# SENSE.net
KiCad netlist of a schematic drawn in Altium Designer
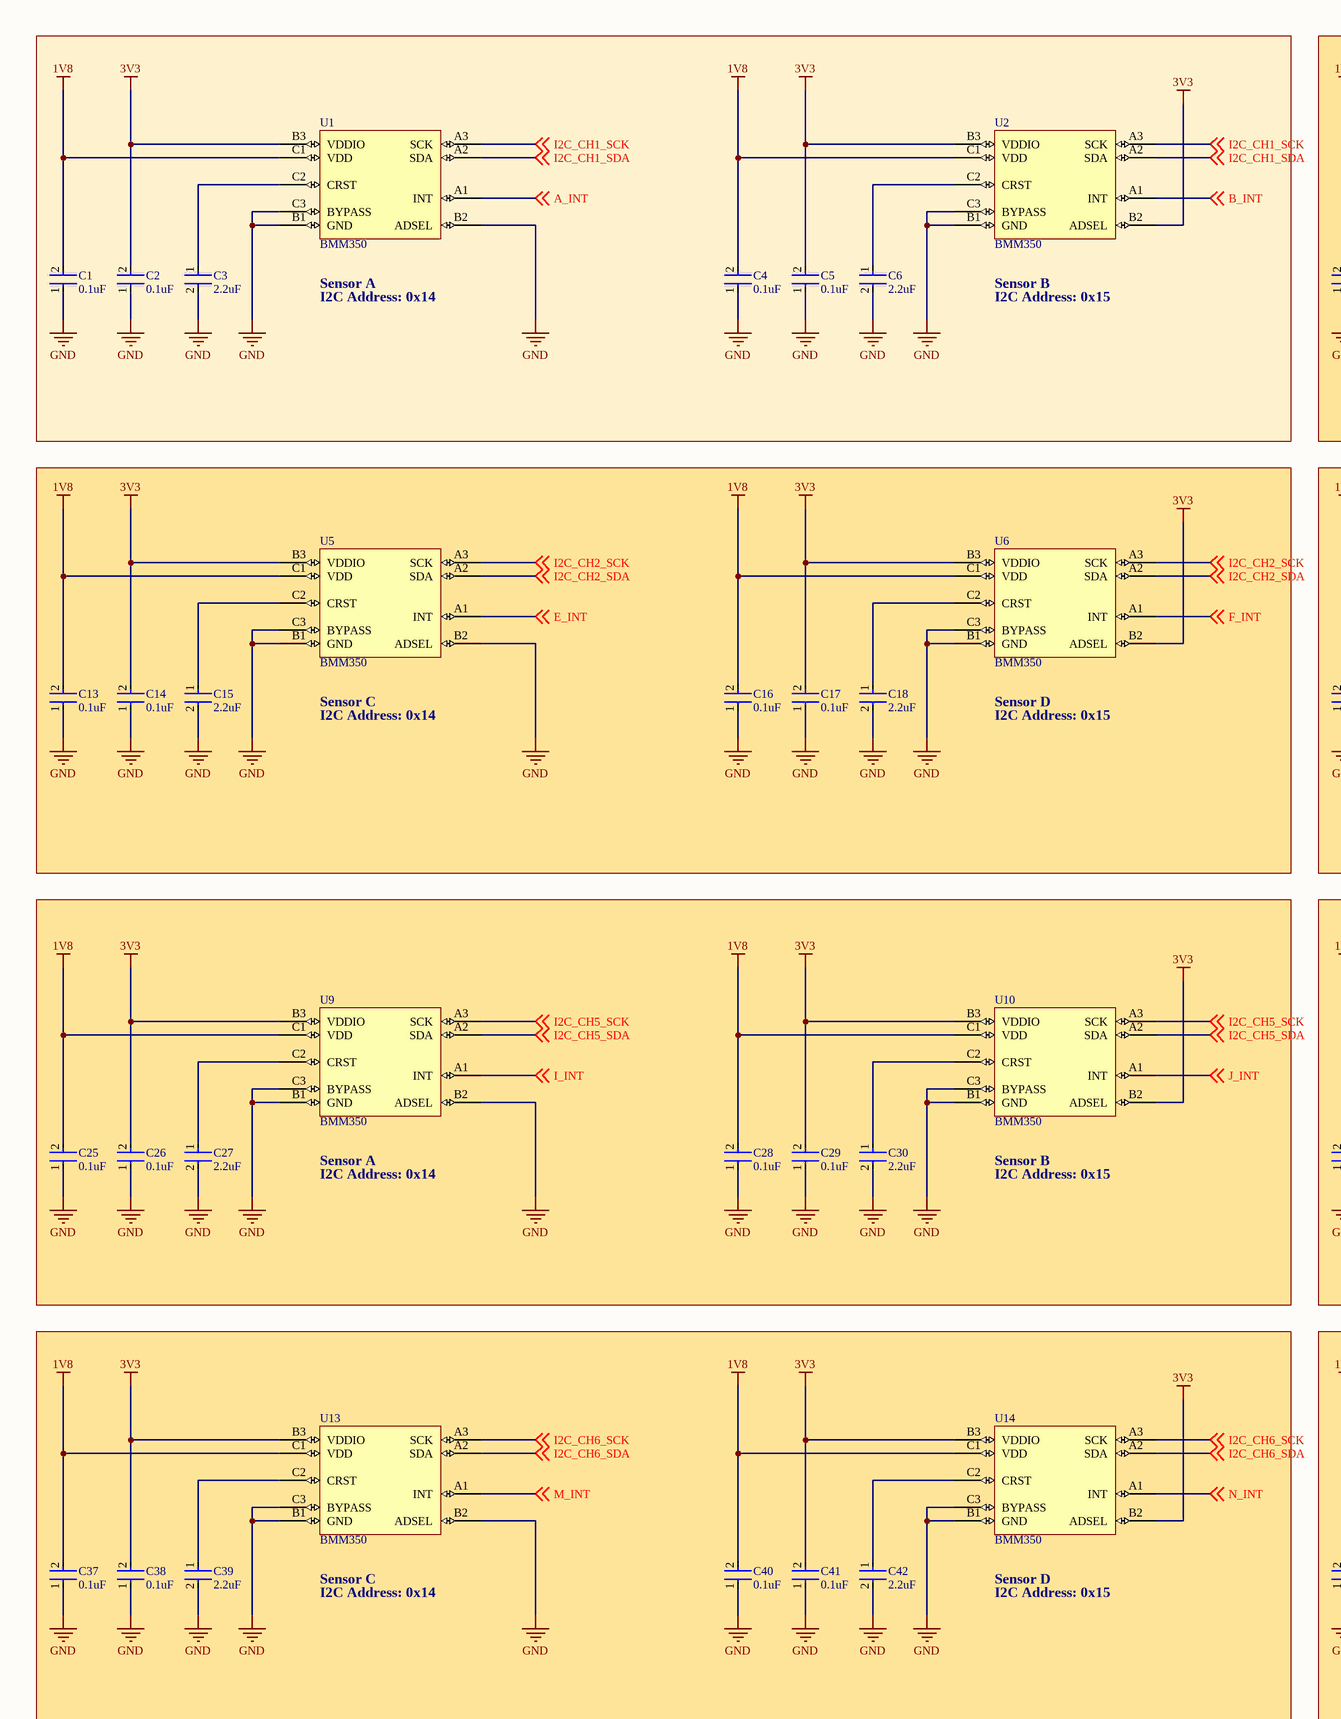
[diagram p0: SENSE.SchDoc, left]
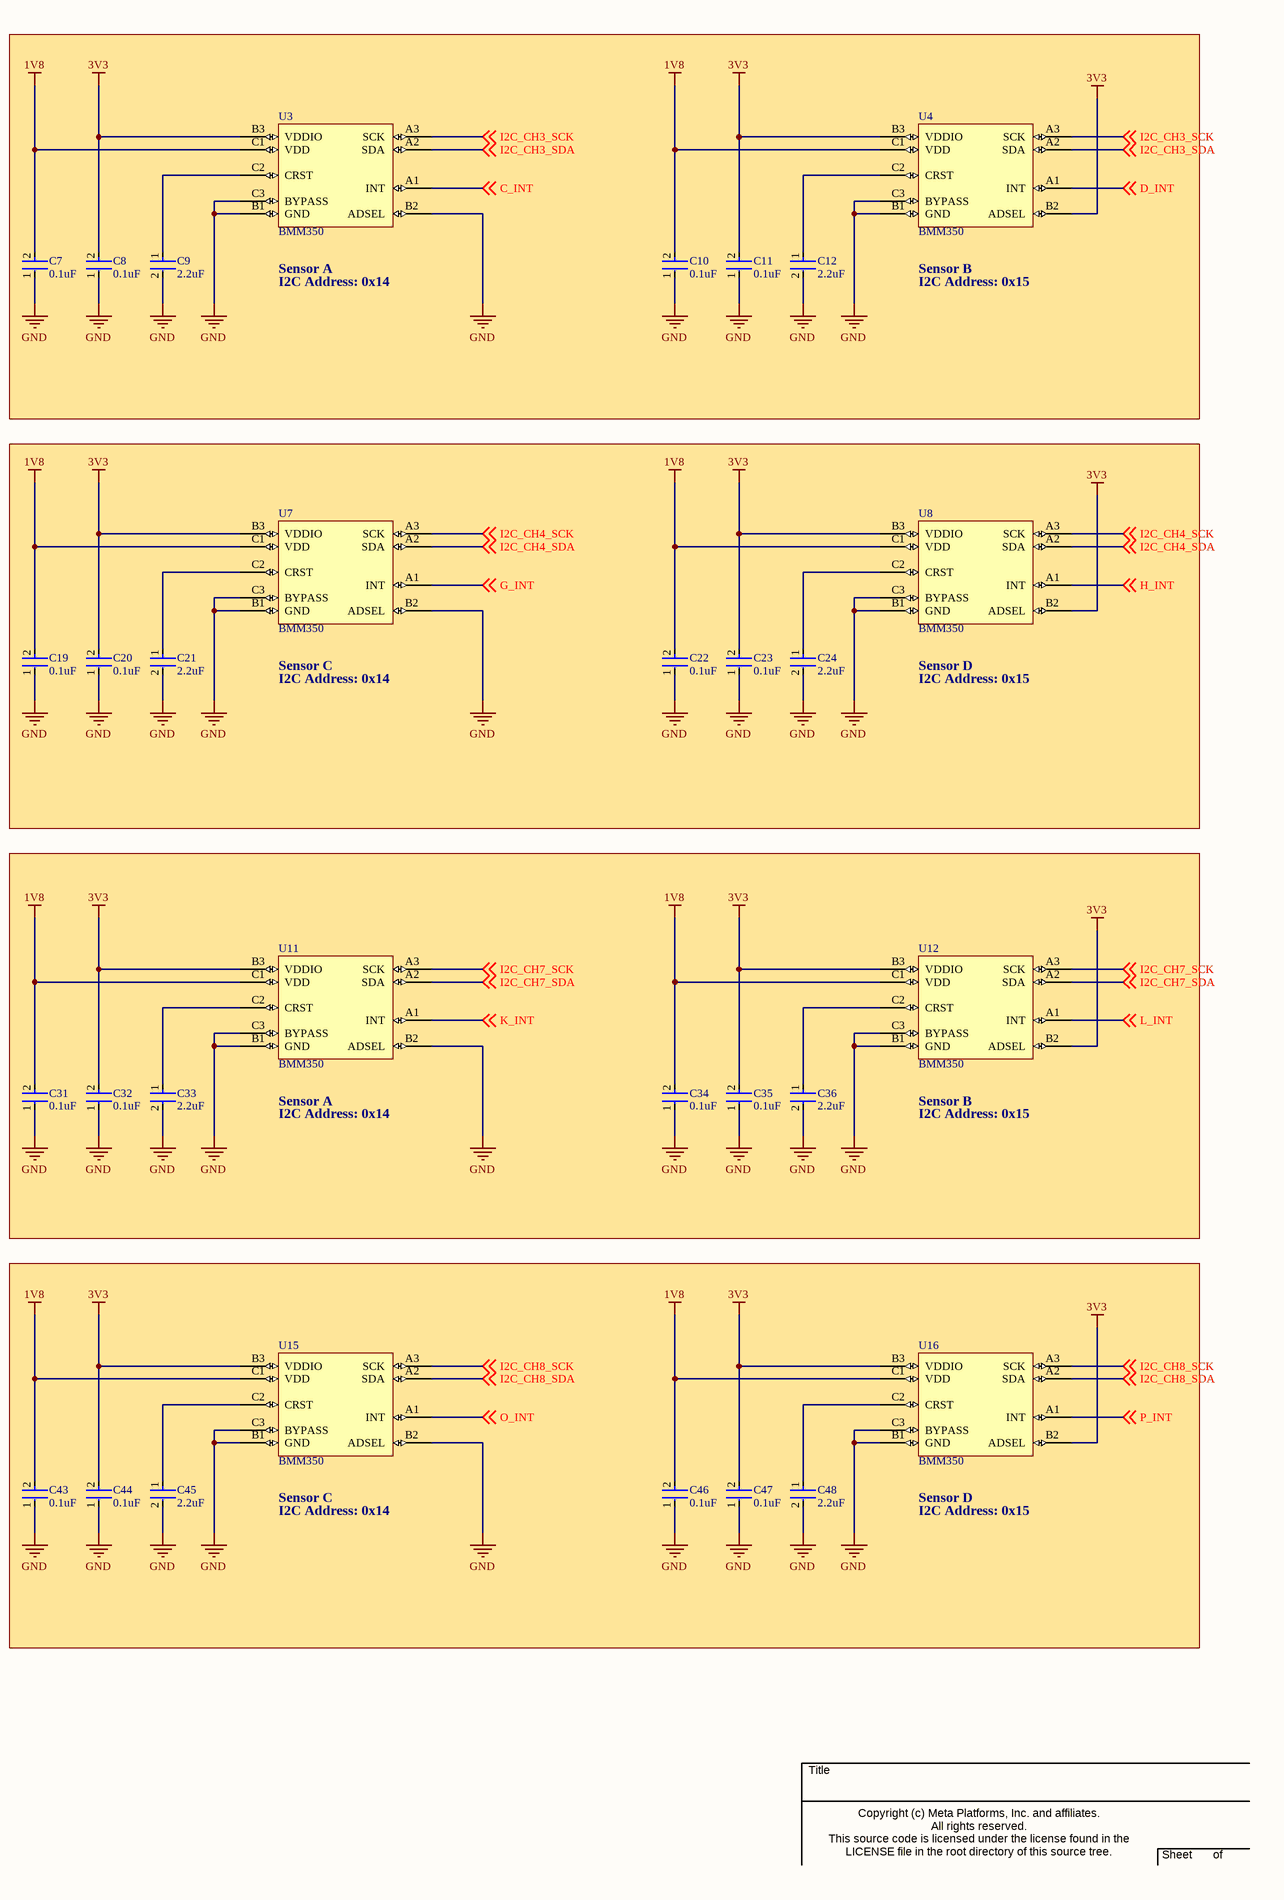
[diagram p1: SENSE.SchDoc, right]

(export (version "E")
  (design (tool "Eeschema 10.0.6"))
  (components
    (comp (ref "C1")
      (value "0.1uF")
      (footprint "FP-GRM15-MFG")
      (description "CAP CER 0.1UF 16V X7R 0402")
      (fields (field (name "MANUFACTURER PART NUMBER") "GRM155R71C104KA88D") (field (name "TOLERANCE") "10%"))
      (libsource (lib "Altium Content Vault") (part "236180d848d6139a670b325ea6854c9"))
    )
    (comp (ref "C2")
      (value "0.1uF")
      (footprint "FP-GRM15-MFG")
      (description "CAP CER 0.1UF 16V X7R 0402")
      (fields (field (name "MANUFACTURER PART NUMBER") "GRM155R71C104KA88D") (field (name "TOLERANCE") "10%"))
      (libsource (lib "Altium Content Vault") (part "236180d848d6139a670b325ea6854c9"))
    )
    (comp (ref "C3")
      (value "2.2uF")
      (footprint "FP-C1005-050-0_15-0_1-MFG")
      (description "CAP CER 2.2UF 10V X7S 0402")
      (fields (field (name "TOLERANCE") "10%"))
      (libsource (lib "Altium Content Vault") (part "b4654b650e69147ec39a6b967a45e02"))
    )
    (comp (ref "C4")
      (value "0.1uF")
      (footprint "FP-GRM15-MFG")
      (description "CAP CER 0.1UF 16V X7R 0402")
      (fields (field (name "MANUFACTURER PART NUMBER") "GRM155R71C104KA88D") (field (name "TOLERANCE") "10%"))
      (libsource (lib "Altium Content Vault") (part "236180d848d6139a670b325ea6854c9"))
    )
    (comp (ref "C5")
      (value "0.1uF")
      (footprint "FP-GRM15-MFG")
      (description "CAP CER 0.1UF 16V X7R 0402")
      (fields (field (name "MANUFACTURER PART NUMBER") "GRM155R71C104KA88D") (field (name "TOLERANCE") "10%"))
      (libsource (lib "Altium Content Vault") (part "236180d848d6139a670b325ea6854c9"))
    )
    (comp (ref "C6")
      (value "2.2uF")
      (footprint "FP-C1005-050-0_15-0_1-MFG")
      (description "CAP CER 2.2UF 10V X7S 0402")
      (fields (field (name "TOLERANCE") "10%"))
      (libsource (lib "Altium Content Vault") (part "b4654b650e69147ec39a6b967a45e02"))
    )
    (comp (ref "C7")
      (value "0.1uF")
      (footprint "FP-GRM15-MFG")
      (description "CAP CER 0.1UF 16V X7R 0402")
      (fields (field (name "MANUFACTURER PART NUMBER") "GRM155R71C104KA88D") (field (name "TOLERANCE") "10%"))
      (libsource (lib "Altium Content Vault") (part "236180d848d6139a670b325ea6854c9"))
    )
    (comp (ref "C8")
      (value "0.1uF")
      (footprint "FP-GRM15-MFG")
      (description "CAP CER 0.1UF 16V X7R 0402")
      (fields (field (name "MANUFACTURER PART NUMBER") "GRM155R71C104KA88D") (field (name "TOLERANCE") "10%"))
      (libsource (lib "Altium Content Vault") (part "236180d848d6139a670b325ea6854c9"))
    )
    (comp (ref "C9")
      (value "2.2uF")
      (footprint "FP-C1005-050-0_15-0_1-MFG")
      (description "CAP CER 2.2UF 10V X7S 0402")
      (fields (field (name "TOLERANCE") "10%"))
      (libsource (lib "Altium Content Vault") (part "b4654b650e69147ec39a6b967a45e02"))
    )
    (comp (ref "C10")
      (value "0.1uF")
      (footprint "FP-GRM15-MFG")
      (description "CAP CER 0.1UF 16V X7R 0402")
      (fields (field (name "MANUFACTURER PART NUMBER") "GRM155R71C104KA88D") (field (name "TOLERANCE") "10%"))
      (libsource (lib "Altium Content Vault") (part "236180d848d6139a670b325ea6854c9"))
    )
    (comp (ref "C11")
      (value "0.1uF")
      (footprint "FP-GRM15-MFG")
      (description "CAP CER 0.1UF 16V X7R 0402")
      (fields (field (name "MANUFACTURER PART NUMBER") "GRM155R71C104KA88D") (field (name "TOLERANCE") "10%"))
      (libsource (lib "Altium Content Vault") (part "236180d848d6139a670b325ea6854c9"))
    )
    (comp (ref "C12")
      (value "2.2uF")
      (footprint "FP-C1005-050-0_15-0_1-MFG")
      (description "CAP CER 2.2UF 10V X7S 0402")
      (fields (field (name "TOLERANCE") "10%"))
      (libsource (lib "Altium Content Vault") (part "b4654b650e69147ec39a6b967a45e02"))
    )
    (comp (ref "C13")
      (value "0.1uF")
      (footprint "FP-GRM15-MFG")
      (description "CAP CER 0.1UF 16V X7R 0402")
      (fields (field (name "MANUFACTURER PART NUMBER") "GRM155R71C104KA88D") (field (name "TOLERANCE") "10%"))
      (libsource (lib "Altium Content Vault") (part "236180d848d6139a670b325ea6854c9"))
    )
    (comp (ref "C14")
      (value "0.1uF")
      (footprint "FP-GRM15-MFG")
      (description "CAP CER 0.1UF 16V X7R 0402")
      (fields (field (name "MANUFACTURER PART NUMBER") "GRM155R71C104KA88D") (field (name "TOLERANCE") "10%"))
      (libsource (lib "Altium Content Vault") (part "236180d848d6139a670b325ea6854c9"))
    )
    (comp (ref "C15")
      (value "2.2uF")
      (footprint "FP-C1005-050-0_15-0_1-MFG")
      (description "CAP CER 2.2UF 10V X7S 0402")
      (fields (field (name "TOLERANCE") "10%"))
      (libsource (lib "Altium Content Vault") (part "b4654b650e69147ec39a6b967a45e02"))
    )
    (comp (ref "C16")
      (value "0.1uF")
      (footprint "FP-GRM15-MFG")
      (description "CAP CER 0.1UF 16V X7R 0402")
      (fields (field (name "MANUFACTURER PART NUMBER") "GRM155R71C104KA88D") (field (name "TOLERANCE") "10%"))
      (libsource (lib "Altium Content Vault") (part "236180d848d6139a670b325ea6854c9"))
    )
    (comp (ref "C17")
      (value "0.1uF")
      (footprint "FP-GRM15-MFG")
      (description "CAP CER 0.1UF 16V X7R 0402")
      (fields (field (name "MANUFACTURER PART NUMBER") "GRM155R71C104KA88D") (field (name "TOLERANCE") "10%"))
      (libsource (lib "Altium Content Vault") (part "236180d848d6139a670b325ea6854c9"))
    )
    (comp (ref "C18")
      (value "2.2uF")
      (footprint "FP-C1005-050-0_15-0_1-MFG")
      (description "CAP CER 2.2UF 10V X7S 0402")
      (fields (field (name "TOLERANCE") "10%"))
      (libsource (lib "Altium Content Vault") (part "b4654b650e69147ec39a6b967a45e02"))
    )
    (comp (ref "C19")
      (value "0.1uF")
      (footprint "FP-GRM15-MFG")
      (description "CAP CER 0.1UF 16V X7R 0402")
      (fields (field (name "MANUFACTURER PART NUMBER") "GRM155R71C104KA88D") (field (name "TOLERANCE") "10%"))
      (libsource (lib "Altium Content Vault") (part "236180d848d6139a670b325ea6854c9"))
    )
    (comp (ref "C20")
      (value "0.1uF")
      (footprint "FP-GRM15-MFG")
      (description "CAP CER 0.1UF 16V X7R 0402")
      (fields (field (name "MANUFACTURER PART NUMBER") "GRM155R71C104KA88D") (field (name "TOLERANCE") "10%"))
      (libsource (lib "Altium Content Vault") (part "236180d848d6139a670b325ea6854c9"))
    )
    (comp (ref "C21")
      (value "2.2uF")
      (footprint "FP-C1005-050-0_15-0_1-MFG")
      (description "CAP CER 2.2UF 10V X7S 0402")
      (fields (field (name "TOLERANCE") "10%"))
      (libsource (lib "Altium Content Vault") (part "b4654b650e69147ec39a6b967a45e02"))
    )
    (comp (ref "C22")
      (value "0.1uF")
      (footprint "FP-GRM15-MFG")
      (description "CAP CER 0.1UF 16V X7R 0402")
      (fields (field (name "MANUFACTURER PART NUMBER") "GRM155R71C104KA88D") (field (name "TOLERANCE") "10%"))
      (libsource (lib "Altium Content Vault") (part "236180d848d6139a670b325ea6854c9"))
    )
    (comp (ref "C23")
      (value "0.1uF")
      (footprint "FP-GRM15-MFG")
      (description "CAP CER 0.1UF 16V X7R 0402")
      (fields (field (name "MANUFACTURER PART NUMBER") "GRM155R71C104KA88D") (field (name "TOLERANCE") "10%"))
      (libsource (lib "Altium Content Vault") (part "236180d848d6139a670b325ea6854c9"))
    )
    (comp (ref "C24")
      (value "2.2uF")
      (footprint "FP-C1005-050-0_15-0_1-MFG")
      (description "CAP CER 2.2UF 10V X7S 0402")
      (fields (field (name "TOLERANCE") "10%"))
      (libsource (lib "Altium Content Vault") (part "b4654b650e69147ec39a6b967a45e02"))
    )
    (comp (ref "C25")
      (value "0.1uF")
      (footprint "FP-GRM15-MFG")
      (description "CAP CER 0.1UF 16V X7R 0402")
      (fields (field (name "MANUFACTURER PART NUMBER") "GRM155R71C104KA88D") (field (name "TOLERANCE") "10%"))
      (libsource (lib "Altium Content Vault") (part "236180d848d6139a670b325ea6854c9"))
    )
    (comp (ref "C26")
      (value "0.1uF")
      (footprint "FP-GRM15-MFG")
      (description "CAP CER 0.1UF 16V X7R 0402")
      (fields (field (name "MANUFACTURER PART NUMBER") "GRM155R71C104KA88D") (field (name "TOLERANCE") "10%"))
      (libsource (lib "Altium Content Vault") (part "236180d848d6139a670b325ea6854c9"))
    )
    (comp (ref "C27")
      (value "2.2uF")
      (footprint "FP-C1005-050-0_15-0_1-MFG")
      (description "CAP CER 2.2UF 10V X7S 0402")
      (fields (field (name "TOLERANCE") "10%"))
      (libsource (lib "Altium Content Vault") (part "b4654b650e69147ec39a6b967a45e02"))
    )
    (comp (ref "C28")
      (value "0.1uF")
      (footprint "FP-GRM15-MFG")
      (description "CAP CER 0.1UF 16V X7R 0402")
      (fields (field (name "MANUFACTURER PART NUMBER") "GRM155R71C104KA88D") (field (name "TOLERANCE") "10%"))
      (libsource (lib "Altium Content Vault") (part "236180d848d6139a670b325ea6854c9"))
    )
    (comp (ref "C29")
      (value "0.1uF")
      (footprint "FP-GRM15-MFG")
      (description "CAP CER 0.1UF 16V X7R 0402")
      (fields (field (name "MANUFACTURER PART NUMBER") "GRM155R71C104KA88D") (field (name "TOLERANCE") "10%"))
      (libsource (lib "Altium Content Vault") (part "236180d848d6139a670b325ea6854c9"))
    )
    (comp (ref "C30")
      (value "2.2uF")
      (footprint "FP-C1005-050-0_15-0_1-MFG")
      (description "CAP CER 2.2UF 10V X7S 0402")
      (fields (field (name "TOLERANCE") "10%"))
      (libsource (lib "Altium Content Vault") (part "b4654b650e69147ec39a6b967a45e02"))
    )
    (comp (ref "C31")
      (value "0.1uF")
      (footprint "FP-GRM15-MFG")
      (description "CAP CER 0.1UF 16V X7R 0402")
      (fields (field (name "MANUFACTURER PART NUMBER") "GRM155R71C104KA88D") (field (name "TOLERANCE") "10%"))
      (libsource (lib "Altium Content Vault") (part "236180d848d6139a670b325ea6854c9"))
    )
    (comp (ref "C32")
      (value "0.1uF")
      (footprint "FP-GRM15-MFG")
      (description "CAP CER 0.1UF 16V X7R 0402")
      (fields (field (name "MANUFACTURER PART NUMBER") "GRM155R71C104KA88D") (field (name "TOLERANCE") "10%"))
      (libsource (lib "Altium Content Vault") (part "236180d848d6139a670b325ea6854c9"))
    )
    (comp (ref "C33")
      (value "2.2uF")
      (footprint "FP-C1005-050-0_15-0_1-MFG")
      (description "CAP CER 2.2UF 10V X7S 0402")
      (fields (field (name "TOLERANCE") "10%"))
      (libsource (lib "Altium Content Vault") (part "b4654b650e69147ec39a6b967a45e02"))
    )
    (comp (ref "C34")
      (value "0.1uF")
      (footprint "FP-GRM15-MFG")
      (description "CAP CER 0.1UF 16V X7R 0402")
      (fields (field (name "MANUFACTURER PART NUMBER") "GRM155R71C104KA88D") (field (name "TOLERANCE") "10%"))
      (libsource (lib "Altium Content Vault") (part "236180d848d6139a670b325ea6854c9"))
    )
    (comp (ref "C35")
      (value "0.1uF")
      (footprint "FP-GRM15-MFG")
      (description "CAP CER 0.1UF 16V X7R 0402")
      (fields (field (name "MANUFACTURER PART NUMBER") "GRM155R71C104KA88D") (field (name "TOLERANCE") "10%"))
      (libsource (lib "Altium Content Vault") (part "236180d848d6139a670b325ea6854c9"))
    )
    (comp (ref "C36")
      (value "2.2uF")
      (footprint "FP-C1005-050-0_15-0_1-MFG")
      (description "CAP CER 2.2UF 10V X7S 0402")
      (fields (field (name "TOLERANCE") "10%"))
      (libsource (lib "Altium Content Vault") (part "b4654b650e69147ec39a6b967a45e02"))
    )
    (comp (ref "C37")
      (value "0.1uF")
      (footprint "FP-GRM15-MFG")
      (description "CAP CER 0.1UF 16V X7R 0402")
      (fields (field (name "MANUFACTURER PART NUMBER") "GRM155R71C104KA88D") (field (name "TOLERANCE") "10%"))
      (libsource (lib "Altium Content Vault") (part "236180d848d6139a670b325ea6854c9"))
    )
    (comp (ref "C38")
      (value "0.1uF")
      (footprint "FP-GRM15-MFG")
      (description "CAP CER 0.1UF 16V X7R 0402")
      (fields (field (name "MANUFACTURER PART NUMBER") "GRM155R71C104KA88D") (field (name "TOLERANCE") "10%"))
      (libsource (lib "Altium Content Vault") (part "236180d848d6139a670b325ea6854c9"))
    )
    (comp (ref "C39")
      (value "2.2uF")
      (footprint "FP-C1005-050-0_15-0_1-MFG")
      (description "CAP CER 2.2UF 10V X7S 0402")
      (fields (field (name "TOLERANCE") "10%"))
      (libsource (lib "Altium Content Vault") (part "b4654b650e69147ec39a6b967a45e02"))
    )
    (comp (ref "C40")
      (value "0.1uF")
      (footprint "FP-GRM15-MFG")
      (description "CAP CER 0.1UF 16V X7R 0402")
      (fields (field (name "MANUFACTURER PART NUMBER") "GRM155R71C104KA88D") (field (name "TOLERANCE") "10%"))
      (libsource (lib "Altium Content Vault") (part "236180d848d6139a670b325ea6854c9"))
    )
    (comp (ref "C41")
      (value "0.1uF")
      (footprint "FP-GRM15-MFG")
      (description "CAP CER 0.1UF 16V X7R 0402")
      (fields (field (name "MANUFACTURER PART NUMBER") "GRM155R71C104KA88D") (field (name "TOLERANCE") "10%"))
      (libsource (lib "Altium Content Vault") (part "236180d848d6139a670b325ea6854c9"))
    )
    (comp (ref "C42")
      (value "2.2uF")
      (footprint "FP-C1005-050-0_15-0_1-MFG")
      (description "CAP CER 2.2UF 10V X7S 0402")
      (fields (field (name "TOLERANCE") "10%"))
      (libsource (lib "Altium Content Vault") (part "b4654b650e69147ec39a6b967a45e02"))
    )
    (comp (ref "C43")
      (value "0.1uF")
      (footprint "FP-GRM15-MFG")
      (description "CAP CER 0.1UF 16V X7R 0402")
      (fields (field (name "MANUFACTURER PART NUMBER") "GRM155R71C104KA88D") (field (name "TOLERANCE") "10%"))
      (libsource (lib "Altium Content Vault") (part "236180d848d6139a670b325ea6854c9"))
    )
    (comp (ref "C44")
      (value "0.1uF")
      (footprint "FP-GRM15-MFG")
      (description "CAP CER 0.1UF 16V X7R 0402")
      (fields (field (name "MANUFACTURER PART NUMBER") "GRM155R71C104KA88D") (field (name "TOLERANCE") "10%"))
      (libsource (lib "Altium Content Vault") (part "236180d848d6139a670b325ea6854c9"))
    )
    (comp (ref "C45")
      (value "2.2uF")
      (footprint "FP-C1005-050-0_15-0_1-MFG")
      (description "CAP CER 2.2UF 10V X7S 0402")
      (fields (field (name "TOLERANCE") "10%"))
      (libsource (lib "Altium Content Vault") (part "b4654b650e69147ec39a6b967a45e02"))
    )
    (comp (ref "C46")
      (value "0.1uF")
      (footprint "FP-GRM15-MFG")
      (description "CAP CER 0.1UF 16V X7R 0402")
      (fields (field (name "MANUFACTURER PART NUMBER") "GRM155R71C104KA88D") (field (name "TOLERANCE") "10%"))
      (libsource (lib "Altium Content Vault") (part "236180d848d6139a670b325ea6854c9"))
    )
    (comp (ref "C47")
      (value "0.1uF")
      (footprint "FP-GRM15-MFG")
      (description "CAP CER 0.1UF 16V X7R 0402")
      (fields (field (name "MANUFACTURER PART NUMBER") "GRM155R71C104KA88D") (field (name "TOLERANCE") "10%"))
      (libsource (lib "Altium Content Vault") (part "236180d848d6139a670b325ea6854c9"))
    )
    (comp (ref "C48")
      (value "2.2uF")
      (footprint "FP-C1005-050-0_15-0_1-MFG")
      (description "CAP CER 2.2UF 10V X7S 0402")
      (fields (field (name "TOLERANCE") "10%"))
      (libsource (lib "Altium Content Vault") (part "b4654b650e69147ec39a6b967a45e02"))
    )
    (comp (ref "U1") (value "BMM350") (footprint "BMM350") (libsource (lib "bmm350") (part "BMM350")))
    (comp (ref "U2") (value "BMM350") (footprint "BMM350") (libsource (lib "bmm350") (part "BMM350")))
    (comp (ref "U3") (value "BMM350") (footprint "BMM350") (libsource (lib "bmm350") (part "BMM350")))
    (comp (ref "U4") (value "BMM350") (footprint "BMM350") (libsource (lib "bmm350") (part "BMM350")))
    (comp (ref "U5") (value "BMM350") (footprint "BMM350") (libsource (lib "bmm350") (part "BMM350")))
    (comp (ref "U6") (value "BMM350") (footprint "BMM350") (libsource (lib "bmm350") (part "BMM350")))
    (comp (ref "U7") (value "BMM350") (footprint "BMM350") (libsource (lib "bmm350") (part "BMM350")))
    (comp (ref "U8") (value "BMM350") (footprint "BMM350") (libsource (lib "bmm350") (part "BMM350")))
    (comp (ref "U9") (value "BMM350") (footprint "BMM350") (libsource (lib "bmm350") (part "BMM350")))
    (comp (ref "U10") (value "BMM350") (footprint "BMM350") (libsource (lib "bmm350") (part "BMM350")))
    (comp (ref "U11") (value "BMM350") (footprint "BMM350") (libsource (lib "bmm350") (part "BMM350")))
    (comp (ref "U12") (value "BMM350") (footprint "BMM350") (libsource (lib "bmm350") (part "BMM350")))
    (comp (ref "U13") (value "BMM350") (footprint "BMM350") (libsource (lib "bmm350") (part "BMM350")))
    (comp (ref "U14") (value "BMM350") (footprint "BMM350") (libsource (lib "bmm350") (part "BMM350")))
    (comp (ref "U15") (value "BMM350") (footprint "BMM350") (libsource (lib "bmm350") (part "BMM350")))
    (comp (ref "U16") (value "BMM350") (footprint "BMM350") (libsource (lib "bmm350") (part "BMM350")))
  )
  (nets
    (net (code "1") (name "1V8") (class "Default")
      (node (ref "C1") (pin "2") (pinfunction "2_2") (pintype "passive"))
      (node (ref "C10") (pin "2") (pinfunction "2_2") (pintype "passive"))
      (node (ref "C13") (pin "2") (pinfunction "2_2") (pintype "passive"))
      (node (ref "C16") (pin "2") (pinfunction "2_2") (pintype "passive"))
      (node (ref "C19") (pin "2") (pinfunction "2_2") (pintype "passive"))
      (node (ref "C22") (pin "2") (pinfunction "2_2") (pintype "passive"))
      (node (ref "C25") (pin "2") (pinfunction "2_2") (pintype "passive"))
      (node (ref "C28") (pin "2") (pinfunction "2_2") (pintype "passive"))
      (node (ref "C31") (pin "2") (pinfunction "2_2") (pintype "passive"))
      (node (ref "C34") (pin "2") (pinfunction "2_2") (pintype "passive"))
      (node (ref "C37") (pin "2") (pinfunction "2_2") (pintype "passive"))
      (node (ref "C4") (pin "2") (pinfunction "2_2") (pintype "passive"))
      (node (ref "C40") (pin "2") (pinfunction "2_2") (pintype "passive"))
      (node (ref "C43") (pin "2") (pinfunction "2_2") (pintype "passive"))
      (node (ref "C46") (pin "2") (pinfunction "2_2") (pintype "passive"))
      (node (ref "C7") (pin "2") (pinfunction "2_2") (pintype "passive"))
      (node (ref "U1") (pin "C1") (pinfunction "VDD_C1") (pintype "bidirectional"))
      (node (ref "U10") (pin "C1") (pinfunction "VDD_C1") (pintype "bidirectional"))
      (node (ref "U11") (pin "C1") (pinfunction "VDD_C1") (pintype "bidirectional"))
      (node (ref "U12") (pin "C1") (pinfunction "VDD_C1") (pintype "bidirectional"))
      (node (ref "U13") (pin "C1") (pinfunction "VDD_C1") (pintype "bidirectional"))
      (node (ref "U14") (pin "C1") (pinfunction "VDD_C1") (pintype "bidirectional"))
      (node (ref "U15") (pin "C1") (pinfunction "VDD_C1") (pintype "bidirectional"))
      (node (ref "U16") (pin "C1") (pinfunction "VDD_C1") (pintype "bidirectional"))
      (node (ref "U2") (pin "C1") (pinfunction "VDD_C1") (pintype "bidirectional"))
      (node (ref "U3") (pin "C1") (pinfunction "VDD_C1") (pintype "bidirectional"))
      (node (ref "U4") (pin "C1") (pinfunction "VDD_C1") (pintype "bidirectional"))
      (node (ref "U5") (pin "C1") (pinfunction "VDD_C1") (pintype "bidirectional"))
      (node (ref "U6") (pin "C1") (pinfunction "VDD_C1") (pintype "bidirectional"))
      (node (ref "U7") (pin "C1") (pinfunction "VDD_C1") (pintype "bidirectional"))
      (node (ref "U8") (pin "C1") (pinfunction "VDD_C1") (pintype "bidirectional"))
      (node (ref "U9") (pin "C1") (pinfunction "VDD_C1") (pintype "bidirectional"))
    )
    (net (code "2") (name "3V3") (class "Default")
      (node (ref "C11") (pin "2") (pinfunction "2_2") (pintype "passive"))
      (node (ref "C14") (pin "2") (pinfunction "2_2") (pintype "passive"))
      (node (ref "C17") (pin "2") (pinfunction "2_2") (pintype "passive"))
      (node (ref "C2") (pin "2") (pinfunction "2_2") (pintype "passive"))
      (node (ref "C20") (pin "2") (pinfunction "2_2") (pintype "passive"))
      (node (ref "C23") (pin "2") (pinfunction "2_2") (pintype "passive"))
      (node (ref "C26") (pin "2") (pinfunction "2_2") (pintype "passive"))
      (node (ref "C29") (pin "2") (pinfunction "2_2") (pintype "passive"))
      (node (ref "C32") (pin "2") (pinfunction "2_2") (pintype "passive"))
      (node (ref "C35") (pin "2") (pinfunction "2_2") (pintype "passive"))
      (node (ref "C38") (pin "2") (pinfunction "2_2") (pintype "passive"))
      (node (ref "C41") (pin "2") (pinfunction "2_2") (pintype "passive"))
      (node (ref "C44") (pin "2") (pinfunction "2_2") (pintype "passive"))
      (node (ref "C47") (pin "2") (pinfunction "2_2") (pintype "passive"))
      (node (ref "C5") (pin "2") (pinfunction "2_2") (pintype "passive"))
      (node (ref "C8") (pin "2") (pinfunction "2_2") (pintype "passive"))
      (node (ref "U1") (pin "B3") (pinfunction "VDDIO_B3") (pintype "bidirectional"))
      (node (ref "U10") (pin "B2") (pinfunction "ADSEL_B2") (pintype "bidirectional"))
      (node (ref "U10") (pin "B3") (pinfunction "VDDIO_B3") (pintype "bidirectional"))
      (node (ref "U11") (pin "B3") (pinfunction "VDDIO_B3") (pintype "bidirectional"))
      (node (ref "U12") (pin "B2") (pinfunction "ADSEL_B2") (pintype "bidirectional"))
      (node (ref "U12") (pin "B3") (pinfunction "VDDIO_B3") (pintype "bidirectional"))
      (node (ref "U13") (pin "B3") (pinfunction "VDDIO_B3") (pintype "bidirectional"))
      (node (ref "U14") (pin "B2") (pinfunction "ADSEL_B2") (pintype "bidirectional"))
      (node (ref "U14") (pin "B3") (pinfunction "VDDIO_B3") (pintype "bidirectional"))
      (node (ref "U15") (pin "B3") (pinfunction "VDDIO_B3") (pintype "bidirectional"))
      (node (ref "U16") (pin "B2") (pinfunction "ADSEL_B2") (pintype "bidirectional"))
      (node (ref "U16") (pin "B3") (pinfunction "VDDIO_B3") (pintype "bidirectional"))
      (node (ref "U2") (pin "B2") (pinfunction "ADSEL_B2") (pintype "bidirectional"))
      (node (ref "U2") (pin "B3") (pinfunction "VDDIO_B3") (pintype "bidirectional"))
      (node (ref "U3") (pin "B3") (pinfunction "VDDIO_B3") (pintype "bidirectional"))
      (node (ref "U4") (pin "B2") (pinfunction "ADSEL_B2") (pintype "bidirectional"))
      (node (ref "U4") (pin "B3") (pinfunction "VDDIO_B3") (pintype "bidirectional"))
      (node (ref "U5") (pin "B3") (pinfunction "VDDIO_B3") (pintype "bidirectional"))
      (node (ref "U6") (pin "B2") (pinfunction "ADSEL_B2") (pintype "bidirectional"))
      (node (ref "U6") (pin "B3") (pinfunction "VDDIO_B3") (pintype "bidirectional"))
      (node (ref "U7") (pin "B3") (pinfunction "VDDIO_B3") (pintype "bidirectional"))
      (node (ref "U8") (pin "B2") (pinfunction "ADSEL_B2") (pintype "bidirectional"))
      (node (ref "U8") (pin "B3") (pinfunction "VDDIO_B3") (pintype "bidirectional"))
      (node (ref "U9") (pin "B3") (pinfunction "VDDIO_B3") (pintype "bidirectional"))
    )
    (net (code "3") (name "A_INT") (class "Default")
      (node (ref "U1") (pin "A1") (pinfunction "INT_A1") (pintype "bidirectional"))
    )
    (net (code "4") (name "B_INT") (class "Default")
      (node (ref "U2") (pin "A1") (pinfunction "INT_A1") (pintype "bidirectional"))
    )
    (net (code "5") (name "C_INT") (class "Default")
      (node (ref "U3") (pin "A1") (pinfunction "INT_A1") (pintype "bidirectional"))
    )
    (net (code "6") (name "D_INT") (class "Default")
      (node (ref "U4") (pin "A1") (pinfunction "INT_A1") (pintype "bidirectional"))
    )
    (net (code "7") (name "E_INT") (class "Default")
      (node (ref "U5") (pin "A1") (pinfunction "INT_A1") (pintype "bidirectional"))
    )
    (net (code "8") (name "F_INT") (class "Default")
      (node (ref "U6") (pin "A1") (pinfunction "INT_A1") (pintype "bidirectional"))
    )
    (net (code "9") (name "GND") (class "Default")
      (node (ref "C1") (pin "1") (pinfunction "1_1") (pintype "passive"))
      (node (ref "C10") (pin "1") (pinfunction "1_1") (pintype "passive"))
      (node (ref "C11") (pin "1") (pinfunction "1_1") (pintype "passive"))
      (node (ref "C12") (pin "2") (pinfunction "2_2") (pintype "passive"))
      (node (ref "C13") (pin "1") (pinfunction "1_1") (pintype "passive"))
      (node (ref "C14") (pin "1") (pinfunction "1_1") (pintype "passive"))
      (node (ref "C15") (pin "2") (pinfunction "2_2") (pintype "passive"))
      (node (ref "C16") (pin "1") (pinfunction "1_1") (pintype "passive"))
      (node (ref "C17") (pin "1") (pinfunction "1_1") (pintype "passive"))
      (node (ref "C18") (pin "2") (pinfunction "2_2") (pintype "passive"))
      (node (ref "C19") (pin "1") (pinfunction "1_1") (pintype "passive"))
      (node (ref "C2") (pin "1") (pinfunction "1_1") (pintype "passive"))
      (node (ref "C20") (pin "1") (pinfunction "1_1") (pintype "passive"))
      (node (ref "C21") (pin "2") (pinfunction "2_2") (pintype "passive"))
      (node (ref "C22") (pin "1") (pinfunction "1_1") (pintype "passive"))
      (node (ref "C23") (pin "1") (pinfunction "1_1") (pintype "passive"))
      (node (ref "C24") (pin "2") (pinfunction "2_2") (pintype "passive"))
      (node (ref "C25") (pin "1") (pinfunction "1_1") (pintype "passive"))
      (node (ref "C26") (pin "1") (pinfunction "1_1") (pintype "passive"))
      (node (ref "C27") (pin "2") (pinfunction "2_2") (pintype "passive"))
      (node (ref "C28") (pin "1") (pinfunction "1_1") (pintype "passive"))
      (node (ref "C29") (pin "1") (pinfunction "1_1") (pintype "passive"))
      (node (ref "C3") (pin "2") (pinfunction "2_2") (pintype "passive"))
      (node (ref "C30") (pin "2") (pinfunction "2_2") (pintype "passive"))
      (node (ref "C31") (pin "1") (pinfunction "1_1") (pintype "passive"))
      (node (ref "C32") (pin "1") (pinfunction "1_1") (pintype "passive"))
      (node (ref "C33") (pin "2") (pinfunction "2_2") (pintype "passive"))
      (node (ref "C34") (pin "1") (pinfunction "1_1") (pintype "passive"))
      (node (ref "C35") (pin "1") (pinfunction "1_1") (pintype "passive"))
      (node (ref "C36") (pin "2") (pinfunction "2_2") (pintype "passive"))
      (node (ref "C37") (pin "1") (pinfunction "1_1") (pintype "passive"))
      (node (ref "C38") (pin "1") (pinfunction "1_1") (pintype "passive"))
      (node (ref "C39") (pin "2") (pinfunction "2_2") (pintype "passive"))
      (node (ref "C4") (pin "1") (pinfunction "1_1") (pintype "passive"))
      (node (ref "C40") (pin "1") (pinfunction "1_1") (pintype "passive"))
      (node (ref "C41") (pin "1") (pinfunction "1_1") (pintype "passive"))
      (node (ref "C42") (pin "2") (pinfunction "2_2") (pintype "passive"))
      (node (ref "C43") (pin "1") (pinfunction "1_1") (pintype "passive"))
      (node (ref "C44") (pin "1") (pinfunction "1_1") (pintype "passive"))
      (node (ref "C45") (pin "2") (pinfunction "2_2") (pintype "passive"))
      (node (ref "C46") (pin "1") (pinfunction "1_1") (pintype "passive"))
      (node (ref "C47") (pin "1") (pinfunction "1_1") (pintype "passive"))
      (node (ref "C48") (pin "2") (pinfunction "2_2") (pintype "passive"))
      (node (ref "C5") (pin "1") (pinfunction "1_1") (pintype "passive"))
      (node (ref "C6") (pin "2") (pinfunction "2_2") (pintype "passive"))
      (node (ref "C7") (pin "1") (pinfunction "1_1") (pintype "passive"))
      (node (ref "C8") (pin "1") (pinfunction "1_1") (pintype "passive"))
      (node (ref "C9") (pin "2") (pinfunction "2_2") (pintype "passive"))
      (node (ref "U1") (pin "B1") (pinfunction "GND_B1") (pintype "bidirectional"))
      (node (ref "U1") (pin "B2") (pinfunction "ADSEL_B2") (pintype "bidirectional"))
      (node (ref "U1") (pin "C3") (pinfunction "BYPASS_C3") (pintype "bidirectional"))
      (node (ref "U10") (pin "B1") (pinfunction "GND_B1") (pintype "bidirectional"))
      (node (ref "U10") (pin "C3") (pinfunction "BYPASS_C3") (pintype "bidirectional"))
      (node (ref "U11") (pin "B1") (pinfunction "GND_B1") (pintype "bidirectional"))
      (node (ref "U11") (pin "B2") (pinfunction "ADSEL_B2") (pintype "bidirectional"))
      (node (ref "U11") (pin "C3") (pinfunction "BYPASS_C3") (pintype "bidirectional"))
      (node (ref "U12") (pin "B1") (pinfunction "GND_B1") (pintype "bidirectional"))
      (node (ref "U12") (pin "C3") (pinfunction "BYPASS_C3") (pintype "bidirectional"))
      (node (ref "U13") (pin "B1") (pinfunction "GND_B1") (pintype "bidirectional"))
      (node (ref "U13") (pin "B2") (pinfunction "ADSEL_B2") (pintype "bidirectional"))
      (node (ref "U13") (pin "C3") (pinfunction "BYPASS_C3") (pintype "bidirectional"))
      (node (ref "U14") (pin "B1") (pinfunction "GND_B1") (pintype "bidirectional"))
      (node (ref "U14") (pin "C3") (pinfunction "BYPASS_C3") (pintype "bidirectional"))
      (node (ref "U15") (pin "B1") (pinfunction "GND_B1") (pintype "bidirectional"))
      (node (ref "U15") (pin "B2") (pinfunction "ADSEL_B2") (pintype "bidirectional"))
      (node (ref "U15") (pin "C3") (pinfunction "BYPASS_C3") (pintype "bidirectional"))
      (node (ref "U16") (pin "B1") (pinfunction "GND_B1") (pintype "bidirectional"))
      (node (ref "U16") (pin "C3") (pinfunction "BYPASS_C3") (pintype "bidirectional"))
      (node (ref "U2") (pin "B1") (pinfunction "GND_B1") (pintype "bidirectional"))
      (node (ref "U2") (pin "C3") (pinfunction "BYPASS_C3") (pintype "bidirectional"))
      (node (ref "U3") (pin "B1") (pinfunction "GND_B1") (pintype "bidirectional"))
      (node (ref "U3") (pin "B2") (pinfunction "ADSEL_B2") (pintype "bidirectional"))
      (node (ref "U3") (pin "C3") (pinfunction "BYPASS_C3") (pintype "bidirectional"))
      (node (ref "U4") (pin "B1") (pinfunction "GND_B1") (pintype "bidirectional"))
      (node (ref "U4") (pin "C3") (pinfunction "BYPASS_C3") (pintype "bidirectional"))
      (node (ref "U5") (pin "B1") (pinfunction "GND_B1") (pintype "bidirectional"))
      (node (ref "U5") (pin "B2") (pinfunction "ADSEL_B2") (pintype "bidirectional"))
      (node (ref "U5") (pin "C3") (pinfunction "BYPASS_C3") (pintype "bidirectional"))
      (node (ref "U6") (pin "B1") (pinfunction "GND_B1") (pintype "bidirectional"))
      (node (ref "U6") (pin "C3") (pinfunction "BYPASS_C3") (pintype "bidirectional"))
      (node (ref "U7") (pin "B1") (pinfunction "GND_B1") (pintype "bidirectional"))
      (node (ref "U7") (pin "B2") (pinfunction "ADSEL_B2") (pintype "bidirectional"))
      (node (ref "U7") (pin "C3") (pinfunction "BYPASS_C3") (pintype "bidirectional"))
      (node (ref "U8") (pin "B1") (pinfunction "GND_B1") (pintype "bidirectional"))
      (node (ref "U8") (pin "C3") (pinfunction "BYPASS_C3") (pintype "bidirectional"))
      (node (ref "U9") (pin "B1") (pinfunction "GND_B1") (pintype "bidirectional"))
      (node (ref "U9") (pin "B2") (pinfunction "ADSEL_B2") (pintype "bidirectional"))
      (node (ref "U9") (pin "C3") (pinfunction "BYPASS_C3") (pintype "bidirectional"))
    )
    (net (code "10") (name "G_INT") (class "Default")
      (node (ref "U7") (pin "A1") (pinfunction "INT_A1") (pintype "bidirectional"))
    )
    (net (code "11") (name "H_INT") (class "Default")
      (node (ref "U8") (pin "A1") (pinfunction "INT_A1") (pintype "bidirectional"))
    )
    (net (code "12") (name "I2C_CH1_SCK") (class "Default")
      (node (ref "U1") (pin "A3") (pinfunction "SCK_A3") (pintype "bidirectional"))
      (node (ref "U2") (pin "A3") (pinfunction "SCK_A3") (pintype "bidirectional"))
    )
    (net (code "13") (name "I2C_CH1_SDA") (class "Default")
      (node (ref "U1") (pin "A2") (pinfunction "SDA_A2") (pintype "bidirectional"))
      (node (ref "U2") (pin "A2") (pinfunction "SDA_A2") (pintype "bidirectional"))
    )
    (net (code "14") (name "I2C_CH2_SCK") (class "Default")
      (node (ref "U5") (pin "A3") (pinfunction "SCK_A3") (pintype "bidirectional"))
      (node (ref "U6") (pin "A3") (pinfunction "SCK_A3") (pintype "bidirectional"))
    )
    (net (code "15") (name "I2C_CH2_SDA") (class "Default")
      (node (ref "U5") (pin "A2") (pinfunction "SDA_A2") (pintype "bidirectional"))
      (node (ref "U6") (pin "A2") (pinfunction "SDA_A2") (pintype "bidirectional"))
    )
    (net (code "16") (name "I2C_CH3_SCK") (class "Default")
      (node (ref "U3") (pin "A3") (pinfunction "SCK_A3") (pintype "bidirectional"))
      (node (ref "U4") (pin "A3") (pinfunction "SCK_A3") (pintype "bidirectional"))
    )
    (net (code "17") (name "I2C_CH3_SDA") (class "Default")
      (node (ref "U3") (pin "A2") (pinfunction "SDA_A2") (pintype "bidirectional"))
      (node (ref "U4") (pin "A2") (pinfunction "SDA_A2") (pintype "bidirectional"))
    )
    (net (code "18") (name "I2C_CH4_SCK") (class "Default")
      (node (ref "U7") (pin "A3") (pinfunction "SCK_A3") (pintype "bidirectional"))
      (node (ref "U8") (pin "A3") (pinfunction "SCK_A3") (pintype "bidirectional"))
    )
    (net (code "19") (name "I2C_CH4_SDA") (class "Default")
      (node (ref "U7") (pin "A2") (pinfunction "SDA_A2") (pintype "bidirectional"))
      (node (ref "U8") (pin "A2") (pinfunction "SDA_A2") (pintype "bidirectional"))
    )
    (net (code "20") (name "I2C_CH5_SCK") (class "Default")
      (node (ref "U10") (pin "A3") (pinfunction "SCK_A3") (pintype "bidirectional"))
      (node (ref "U9") (pin "A3") (pinfunction "SCK_A3") (pintype "bidirectional"))
    )
    (net (code "21") (name "I2C_CH5_SDA") (class "Default")
      (node (ref "U10") (pin "A2") (pinfunction "SDA_A2") (pintype "bidirectional"))
      (node (ref "U9") (pin "A2") (pinfunction "SDA_A2") (pintype "bidirectional"))
    )
    (net (code "22") (name "I2C_CH6_SCK") (class "Default")
      (node (ref "U13") (pin "A3") (pinfunction "SCK_A3") (pintype "bidirectional"))
      (node (ref "U14") (pin "A3") (pinfunction "SCK_A3") (pintype "bidirectional"))
    )
    (net (code "23") (name "I2C_CH6_SDA") (class "Default")
      (node (ref "U13") (pin "A2") (pinfunction "SDA_A2") (pintype "bidirectional"))
      (node (ref "U14") (pin "A2") (pinfunction "SDA_A2") (pintype "bidirectional"))
    )
    (net (code "24") (name "I2C_CH7_SCK") (class "Default")
      (node (ref "U11") (pin "A3") (pinfunction "SCK_A3") (pintype "bidirectional"))
      (node (ref "U12") (pin "A3") (pinfunction "SCK_A3") (pintype "bidirectional"))
    )
    (net (code "25") (name "I2C_CH7_SDA") (class "Default")
      (node (ref "U11") (pin "A2") (pinfunction "SDA_A2") (pintype "bidirectional"))
      (node (ref "U12") (pin "A2") (pinfunction "SDA_A2") (pintype "bidirectional"))
    )
    (net (code "26") (name "I2C_CH8_SCK") (class "Default")
      (node (ref "U15") (pin "A3") (pinfunction "SCK_A3") (pintype "bidirectional"))
      (node (ref "U16") (pin "A3") (pinfunction "SCK_A3") (pintype "bidirectional"))
    )
    (net (code "27") (name "I2C_CH8_SDA") (class "Default")
      (node (ref "U15") (pin "A2") (pinfunction "SDA_A2") (pintype "bidirectional"))
      (node (ref "U16") (pin "A2") (pinfunction "SDA_A2") (pintype "bidirectional"))
    )
    (net (code "28") (name "I_INT") (class "Default")
      (node (ref "U9") (pin "A1") (pinfunction "INT_A1") (pintype "bidirectional"))
    )
    (net (code "29") (name "J_INT") (class "Default")
      (node (ref "U10") (pin "A1") (pinfunction "INT_A1") (pintype "bidirectional"))
    )
    (net (code "30") (name "K_INT") (class "Default")
      (node (ref "U11") (pin "A1") (pinfunction "INT_A1") (pintype "bidirectional"))
    )
    (net (code "31") (name "L_INT") (class "Default")
      (node (ref "U12") (pin "A1") (pinfunction "INT_A1") (pintype "bidirectional"))
    )
    (net (code "32") (name "M_INT") (class "Default")
      (node (ref "U13") (pin "A1") (pinfunction "INT_A1") (pintype "bidirectional"))
    )
    (net (code "33") (name "N_INT") (class "Default")
      (node (ref "U14") (pin "A1") (pinfunction "INT_A1") (pintype "bidirectional"))
    )
    (net (code "34") (name "Net-(U1-CRST)") (class "Default")
      (node (ref "C3") (pin "1") (pinfunction "1_1") (pintype "passive"))
      (node (ref "U1") (pin "C2") (pinfunction "CRST_C2") (pintype "bidirectional"))
    )
    (net (code "35") (name "Net-(U2-CRST)") (class "Default")
      (node (ref "C6") (pin "1") (pinfunction "1_1") (pintype "passive"))
      (node (ref "U2") (pin "C2") (pinfunction "CRST_C2") (pintype "bidirectional"))
    )
    (net (code "36") (name "Net-(U3-CRST)") (class "Default")
      (node (ref "C9") (pin "1") (pinfunction "1_1") (pintype "passive"))
      (node (ref "U3") (pin "C2") (pinfunction "CRST_C2") (pintype "bidirectional"))
    )
    (net (code "37") (name "Net-(U4-CRST)") (class "Default")
      (node (ref "C12") (pin "1") (pinfunction "1_1") (pintype "passive"))
      (node (ref "U4") (pin "C2") (pinfunction "CRST_C2") (pintype "bidirectional"))
    )
    (net (code "38") (name "Net-(U5-CRST)") (class "Default")
      (node (ref "C15") (pin "1") (pinfunction "1_1") (pintype "passive"))
      (node (ref "U5") (pin "C2") (pinfunction "CRST_C2") (pintype "bidirectional"))
    )
    (net (code "39") (name "Net-(U6-CRST)") (class "Default")
      (node (ref "C18") (pin "1") (pinfunction "1_1") (pintype "passive"))
      (node (ref "U6") (pin "C2") (pinfunction "CRST_C2") (pintype "bidirectional"))
    )
    (net (code "40") (name "Net-(U7-CRST)") (class "Default")
      (node (ref "C21") (pin "1") (pinfunction "1_1") (pintype "passive"))
      (node (ref "U7") (pin "C2") (pinfunction "CRST_C2") (pintype "bidirectional"))
    )
    (net (code "41") (name "Net-(U8-CRST)") (class "Default")
      (node (ref "C24") (pin "1") (pinfunction "1_1") (pintype "passive"))
      (node (ref "U8") (pin "C2") (pinfunction "CRST_C2") (pintype "bidirectional"))
    )
    (net (code "42") (name "Net-(U9-CRST)") (class "Default")
      (node (ref "C27") (pin "1") (pinfunction "1_1") (pintype "passive"))
      (node (ref "U9") (pin "C2") (pinfunction "CRST_C2") (pintype "bidirectional"))
    )
    (net (code "43") (name "Net-(U10-CRST)") (class "Default")
      (node (ref "C30") (pin "1") (pinfunction "1_1") (pintype "passive"))
      (node (ref "U10") (pin "C2") (pinfunction "CRST_C2") (pintype "bidirectional"))
    )
    (net (code "44") (name "Net-(U11-CRST)") (class "Default")
      (node (ref "C33") (pin "1") (pinfunction "1_1") (pintype "passive"))
      (node (ref "U11") (pin "C2") (pinfunction "CRST_C2") (pintype "bidirectional"))
    )
    (net (code "45") (name "Net-(U12-CRST)") (class "Default")
      (node (ref "C36") (pin "1") (pinfunction "1_1") (pintype "passive"))
      (node (ref "U12") (pin "C2") (pinfunction "CRST_C2") (pintype "bidirectional"))
    )
    (net (code "46") (name "Net-(U13-CRST)") (class "Default")
      (node (ref "C39") (pin "1") (pinfunction "1_1") (pintype "passive"))
      (node (ref "U13") (pin "C2") (pinfunction "CRST_C2") (pintype "bidirectional"))
    )
    (net (code "47") (name "Net-(U14-CRST)") (class "Default")
      (node (ref "C42") (pin "1") (pinfunction "1_1") (pintype "passive"))
      (node (ref "U14") (pin "C2") (pinfunction "CRST_C2") (pintype "bidirectional"))
    )
    (net (code "48") (name "Net-(U15-CRST)") (class "Default")
      (node (ref "C45") (pin "1") (pinfunction "1_1") (pintype "passive"))
      (node (ref "U15") (pin "C2") (pinfunction "CRST_C2") (pintype "bidirectional"))
    )
    (net (code "49") (name "Net-(U16-CRST)") (class "Default")
      (node (ref "C48") (pin "1") (pinfunction "1_1") (pintype "passive"))
      (node (ref "U16") (pin "C2") (pinfunction "CRST_C2") (pintype "bidirectional"))
    )
    (net (code "50") (name "O_INT") (class "Default")
      (node (ref "U15") (pin "A1") (pinfunction "INT_A1") (pintype "bidirectional"))
    )
    (net (code "51") (name "P_INT") (class "Default")
      (node (ref "U16") (pin "A1") (pinfunction "INT_A1") (pintype "bidirectional"))
    )
  )
)
